# POWER.net
KiCad netlist of a schematic drawn in Altium Designer
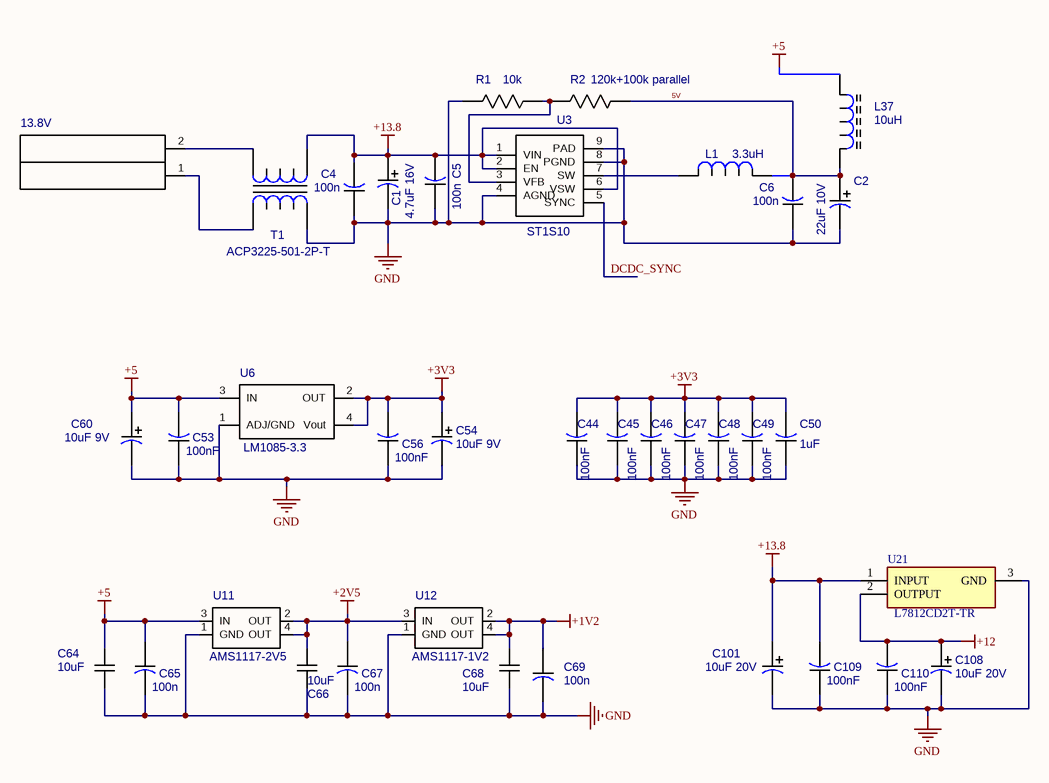
[diagram p0: POWER.SchDoc]

(export (version "E")
  (design (tool "Eeschema 10.0.6"))
  (components
    (comp (ref "13.8V") (value "JX2") (footprint "JX2") (libsource (lib "*") (part "JX2")))
    (comp (ref "C1")
      (value "4.7uF 16V")
      (footprint "CAPAE_6.6x6.6h5.4")
      (description "CAPAE_6.6x6.6h5.4")
      (libsource (lib "*") (part "CAPAE_6.6x6.6h5.4"))
    )
    (comp (ref "C2")
      (value "22uF 10V")
      (footprint "CAPAE_4.3x4.3h5.4")
      (description "CAPAE_4.3x4.3h5.4")
      (libsource (lib "*") (part "CAPAE_4.3x4.3h5.4"))
    )
    (comp (ref "C4")
      (value "100n")
      (footprint "CAP_0805")
      (description "CAP_0805")
      (libsource (lib "*") (part "CAP_0805"))
    )
    (comp (ref "C5")
      (value "100n")
      (footprint "CAP_0805")
      (description "CAP_0805")
      (libsource (lib "*") (part "CAP_0805"))
    )
    (comp (ref "C6")
      (value "100n")
      (footprint "CAP_0805")
      (description "CAP_0805")
      (libsource (lib "*") (part "CAP_0805"))
    )
    (comp (ref "C44")
      (value "100nF")
      (footprint "CAP_0805")
      (description "CAP_0805")
      (libsource (lib "*") (part "CAP_0805"))
    )
    (comp (ref "C45")
      (value "100nF")
      (footprint "CAP_0805")
      (description "CAP_0805")
      (libsource (lib "*") (part "CAP_0805"))
    )
    (comp (ref "C46")
      (value "100nF")
      (footprint "CAP_0805")
      (description "CAP_0805")
      (libsource (lib "*") (part "CAP_0805"))
    )
    (comp (ref "C47")
      (value "100nF")
      (footprint "CAP_0805")
      (description "CAP_0805")
      (libsource (lib "*") (part "CAP_0805"))
    )
    (comp (ref "C48")
      (value "100nF")
      (footprint "CAP_0805")
      (description "CAP_0805")
      (libsource (lib "*") (part "CAP_0805"))
    )
    (comp (ref "C49")
      (value "100nF")
      (footprint "CAP_0805")
      (description "CAP_0805")
      (libsource (lib "*") (part "CAP_0805"))
    )
    (comp (ref "C50")
      (value "1uF")
      (footprint "CAP_0805")
      (description "CAP_0805")
      (fields (field (name "Comment") "10uF"))
      (libsource (lib "*") (part "CAP_0805"))
    )
    (comp (ref "C53")
      (value "100nF")
      (footprint "CAP_0805")
      (description "CAP_0805")
      (libsource (lib "*") (part "CAP_0805"))
    )
    (comp (ref "C54")
      (value "10uF 9V")
      (footprint "CAPAE_4.3x4.3h5.4")
      (description "CAPAE_4.3x4.3h5.4")
      (libsource (lib "*") (part "CAPAE_4.3x4.3h5.4"))
    )
    (comp (ref "C56")
      (value "100nF")
      (footprint "CAP_0805")
      (description "CAP_0805")
      (libsource (lib "*") (part "CAP_0805"))
    )
    (comp (ref "C60")
      (value "10uF 9V")
      (footprint "CAPAE_4.3x4.3h5.4")
      (description "CAPAE_4.3x4.3h5.4")
      (libsource (lib "*") (part "CAPAE_4.3x4.3h5.4"))
    )
    (comp (ref "C64")
      (value "10uF")
      (footprint "C0805")
      (description "C0805")
      (libsource (lib "*") (part "C0805"))
    )
    (comp (ref "C65")
      (value "100n")
      (footprint "CAP_0805")
      (description "CAP_0805")
      (libsource (lib "*") (part "CAP_0805"))
    )
    (comp (ref "C66")
      (value "10uF")
      (footprint "C0805")
      (description "C0805")
      (libsource (lib "*") (part "C0805"))
    )
    (comp (ref "C67")
      (value "100n")
      (footprint "CAP_0805")
      (description "CAP_0805")
      (libsource (lib "*") (part "CAP_0805"))
    )
    (comp (ref "C68")
      (value "10uF")
      (footprint "C0805")
      (description "C0805")
      (libsource (lib "*") (part "C0805"))
    )
    (comp (ref "C69")
      (value "100n")
      (footprint "CAP_0805")
      (description "CAP_0805")
      (libsource (lib "*") (part "CAP_0805"))
    )
    (comp (ref "C101")
      (value "10uF 20V")
      (footprint "CAPAE_4.3x4.3h5.4")
      (description "CAPAE_4.3x4.3h5.4")
      (libsource (lib "*") (part "CAPAE_4.3x4.3h5.4"))
    )
    (comp (ref "C108")
      (value "10uF 20V")
      (footprint "CAPAE_4.3x4.3h5.4")
      (description "CAPAE_4.3x4.3h5.4")
      (libsource (lib "*") (part "CAPAE_4.3x4.3h5.4"))
    )
    (comp (ref "C109")
      (value "100nF")
      (footprint "CAP_0805")
      (description "CAP_0805")
      (libsource (lib "*") (part "CAP_0805"))
    )
    (comp (ref "C110")
      (value "100nF")
      (footprint "CAP_0805")
      (description "CAP_0805")
      (libsource (lib "*") (part "CAP_0805"))
    )
    (comp (ref "L1")
      (value "3.3uH")
      (footprint "IND_1812")
      (description "IND_1812")
      (libsource (lib "*") (part "IND_1812"))
    )
    (comp (ref "L37")
      (value "10uH")
      (footprint "IND_FERRITE_CORE")
      (description "Inductor")
      (libsource (lib "MOTHERBOARD_1") (part "IND_FERRITE_CORE"))
    )
    (comp (ref "R1")
      (value "10k")
      (footprint "RES_0805")
      (description "RES_0805")
      (libsource (lib "*") (part "RES_0805"))
    )
    (comp (ref "R2")
      (value "120k+100k parallel")
      (footprint "RES_0805")
      (description "RES_0805")
      (fields (field (name "Comment") "120k+100k"))
      (libsource (lib "*") (part "RES_0805"))
    )
    (comp (ref "T1")
      (value "ACP3225-501-2P-T")
      (footprint "TRANSF_ICORE")
      (description "Transformer")
      (libsource (lib "*") (part "TRANSF_ICORE"))
    )
    (comp (ref "U3") (value "ST1S10") (footprint "ST1S10") (libsource (lib "*") (part "ST1S10")))
    (comp (ref "U6") (value "LM1085-3.3") (footprint "LM1085-3.3") (libsource (lib "*") (part "LM1085-3.3")))
    (comp (ref "U11") (value "AMS1117-2V5") (footprint "AMS1117") (libsource (lib "*") (part "AMS1117")))
    (comp (ref "U12") (value "AMS1117-1V2") (footprint "AMS1117") (libsource (lib "*") (part "AMS1117")))
    (comp (ref "U21")
      (value "L7812CD2T-TR")
      (footprint "SamacSys:L7812CD2TTR")
      (description "Integrated Circuit")
      (fields (field (name "MOUSER PART NUMBER") "511-L7812CD2T-TR"))
      (libsource (lib "*") (part "L7812CD2T-TR"))
    )
  )
  (nets
    (net (code "1") (name "+1V2") (class "Default")
      (node (ref "C68") (pin "1") (pinfunction "1_1") (pintype "passive"))
      (node (ref "C69") (pin "1") (pinfunction "1_1") (pintype "passive"))
      (node (ref "U12") (pin "2") (pinfunction "OUT_2") (pintype "passive"))
      (node (ref "U12") (pin "4") (pinfunction "OUT_4") (pintype "passive"))
    )
    (net (code "2") (name "+2V5") (class "Default")
      (node (ref "C66") (pin "1") (pinfunction "1_1") (pintype "passive"))
      (node (ref "C67") (pin "1") (pinfunction "1_1") (pintype "passive"))
      (node (ref "U11") (pin "2") (pinfunction "OUT_2") (pintype "passive"))
      (node (ref "U11") (pin "4") (pinfunction "OUT_4") (pintype "passive"))
      (node (ref "U12") (pin "3") (pinfunction "IN_3") (pintype "passive"))
    )
    (net (code "3") (name "+3V3") (class "Default")
      (node (ref "C44") (pin "2") (pinfunction "2_2") (pintype "passive"))
      (node (ref "C45") (pin "2") (pinfunction "2_2") (pintype "passive"))
      (node (ref "C46") (pin "2") (pinfunction "2_2") (pintype "passive"))
      (node (ref "C47") (pin "2") (pinfunction "2_2") (pintype "passive"))
      (node (ref "C48") (pin "2") (pinfunction "2_2") (pintype "passive"))
      (node (ref "C49") (pin "2") (pinfunction "2_2") (pintype "passive"))
      (node (ref "C50") (pin "2") (pinfunction "2_2") (pintype "passive"))
      (node (ref "C54") (pin "1") (pinfunction "PLUS_1") (pintype "passive"))
      (node (ref "C56") (pin "2") (pinfunction "2_2") (pintype "passive"))
      (node (ref "U6") (pin "2") (pinfunction "OUT_2") (pintype "passive"))
      (node (ref "U6") (pin "4") (pinfunction "Vout_4") (pintype "passive"))
    )
    (net (code "4") (name "+5") (class "Default")
      (node (ref "C53") (pin "2") (pinfunction "2_2") (pintype "passive"))
      (node (ref "C60") (pin "1") (pinfunction "PLUS_1") (pintype "passive"))
      (node (ref "C64") (pin "1") (pinfunction "1_1") (pintype "passive"))
      (node (ref "C65") (pin "1") (pinfunction "1_1") (pintype "passive"))
      (node (ref "L37") (pin "1") (pinfunction "A_1") (pintype "passive"))
      (node (ref "U11") (pin "3") (pinfunction "IN_3") (pintype "passive"))
      (node (ref "U6") (pin "3") (pinfunction "IN_3") (pintype "passive"))
    )
    (net (code "5") (name "+12") (class "Default")
      (node (ref "C108") (pin "1") (pinfunction "PLUS_1") (pintype "passive"))
      (node (ref "C110") (pin "2") (pinfunction "2_2") (pintype "passive"))
      (node (ref "U21") (pin "2") (pinfunction "OUTPUT_2") (pintype "passive"))
    )
    (net (code "6") (name "+13.8") (class "Default")
      (node (ref "C1") (pin "1") (pinfunction "PLUS_1") (pintype "passive"))
      (node (ref "C101") (pin "1") (pinfunction "PLUS_1") (pintype "passive"))
      (node (ref "C109") (pin "2") (pinfunction "2_2") (pintype "passive"))
      (node (ref "C4") (pin "2") (pinfunction "2_2") (pintype "passive"))
      (node (ref "C5") (pin "2") (pinfunction "2_2") (pintype "passive"))
      (node (ref "T1") (pin "3") (pinfunction "P1_3") (pintype "passive"))
      (node (ref "U21") (pin "1") (pinfunction "INPUT_1") (pintype "passive"))
      (node (ref "U3") (pin "1") (pinfunction "VIN_1") (pintype "passive"))
      (node (ref "U3") (pin "2") (pinfunction "EN_2") (pintype "passive"))
      (node (ref "U3") (pin "6") (pinfunction "VSW_6") (pintype "passive"))
    )
    (net (code "7") (name "/5V") (class "Default")
      (node (ref "C2") (pin "1") (pinfunction "PLUS_1") (pintype "passive"))
      (node (ref "C6") (pin "2") (pinfunction "2_2") (pintype "passive"))
      (node (ref "L1") (pin "2") (pinfunction "2_2") (pintype "passive"))
      (node (ref "L37") (pin "2") (pinfunction "B_2") (pintype "passive"))
      (node (ref "R2") (pin "2") (pinfunction "2_2") (pintype "passive"))
    )
    (net (code "8") (name "/DCDC_SYNC") (class "Default")
      (node (ref "U3") (pin "5") (pinfunction "SYNC_5") (pintype "passive"))
    )
    (net (code "9") (name "GND") (class "Default")
      (node (ref "C1") (pin "2") (pinfunction "MINUS_2") (pintype "passive"))
      (node (ref "C101") (pin "2") (pinfunction "MINUS_2") (pintype "passive"))
      (node (ref "C108") (pin "2") (pinfunction "MINUS_2") (pintype "passive"))
      (node (ref "C109") (pin "1") (pinfunction "1_1") (pintype "passive"))
      (node (ref "C110") (pin "1") (pinfunction "1_1") (pintype "passive"))
      (node (ref "C2") (pin "2") (pinfunction "MINUS_2") (pintype "passive"))
      (node (ref "C4") (pin "1") (pinfunction "1_1") (pintype "passive"))
      (node (ref "C44") (pin "1") (pinfunction "1_1") (pintype "passive"))
      (node (ref "C45") (pin "1") (pinfunction "1_1") (pintype "passive"))
      (node (ref "C46") (pin "1") (pinfunction "1_1") (pintype "passive"))
      (node (ref "C47") (pin "1") (pinfunction "1_1") (pintype "passive"))
      (node (ref "C48") (pin "1") (pinfunction "1_1") (pintype "passive"))
      (node (ref "C49") (pin "1") (pinfunction "1_1") (pintype "passive"))
      (node (ref "C5") (pin "1") (pinfunction "1_1") (pintype "passive"))
      (node (ref "C50") (pin "1") (pinfunction "1_1") (pintype "passive"))
      (node (ref "C53") (pin "1") (pinfunction "1_1") (pintype "passive"))
      (node (ref "C54") (pin "2") (pinfunction "MINUS_2") (pintype "passive"))
      (node (ref "C56") (pin "1") (pinfunction "1_1") (pintype "passive"))
      (node (ref "C6") (pin "1") (pinfunction "1_1") (pintype "passive"))
      (node (ref "C60") (pin "2") (pinfunction "MINUS_2") (pintype "passive"))
      (node (ref "C64") (pin "2") (pinfunction "2_2") (pintype "passive"))
      (node (ref "C65") (pin "2") (pinfunction "2_2") (pintype "passive"))
      (node (ref "C66") (pin "2") (pinfunction "2_2") (pintype "passive"))
      (node (ref "C67") (pin "2") (pinfunction "2_2") (pintype "passive"))
      (node (ref "C68") (pin "2") (pinfunction "2_2") (pintype "passive"))
      (node (ref "C69") (pin "2") (pinfunction "2_2") (pintype "passive"))
      (node (ref "R1") (pin "1") (pinfunction "1_1") (pintype "passive"))
      (node (ref "T1") (pin "1") (pinfunction "S1_1") (pintype "passive"))
      (node (ref "U11") (pin "1") (pinfunction "GND_1") (pintype "passive"))
      (node (ref "U12") (pin "1") (pinfunction "GND_1") (pintype "passive"))
      (node (ref "U21") (pin "3") (pinfunction "GND_3") (pintype "passive"))
      (node (ref "U3") (pin "4") (pinfunction "AGND_4") (pintype "passive"))
      (node (ref "U3") (pin "8") (pinfunction "PGND_8") (pintype "passive"))
      (node (ref "U3") (pin "9") (pinfunction "PAD_9") (pintype "passive"))
      (node (ref "U6") (pin "1") (pinfunction "ADJ/GND_1") (pintype "passive"))
    )
    (net (code "10") (name "Net-(13.8V-1)") (class "Default")
      (node (ref "13.8V") (pin "2") (pinfunction "1_2") (pintype "passive"))
      (node (ref "T1") (pin "4") (pinfunction "P2_4") (pintype "passive"))
    )
    (net (code "11") (name "Net-(13.8V-2)") (class "Default")
      (node (ref "13.8V") (pin "1") (pinfunction "2_1") (pintype "passive"))
      (node (ref "T1") (pin "2") (pinfunction "S2_2") (pintype "passive"))
    )
    (net (code "12") (name "Net-(U3-SW)") (class "Default")
      (node (ref "L1") (pin "1") (pinfunction "1_1") (pintype "passive"))
      (node (ref "U3") (pin "7") (pinfunction "SW_7") (pintype "passive"))
    )
    (net (code "13") (name "Net-(U3-VFB)") (class "Default")
      (node (ref "R1") (pin "2") (pinfunction "2_2") (pintype "passive"))
      (node (ref "R2") (pin "1") (pinfunction "1_1") (pintype "passive"))
      (node (ref "U3") (pin "3") (pinfunction "VFB_3") (pintype "passive"))
    )
  )
)
